# STM32WB55_Sensor_MCU.net
KiCad netlist of a schematic drawn in Altium Designer
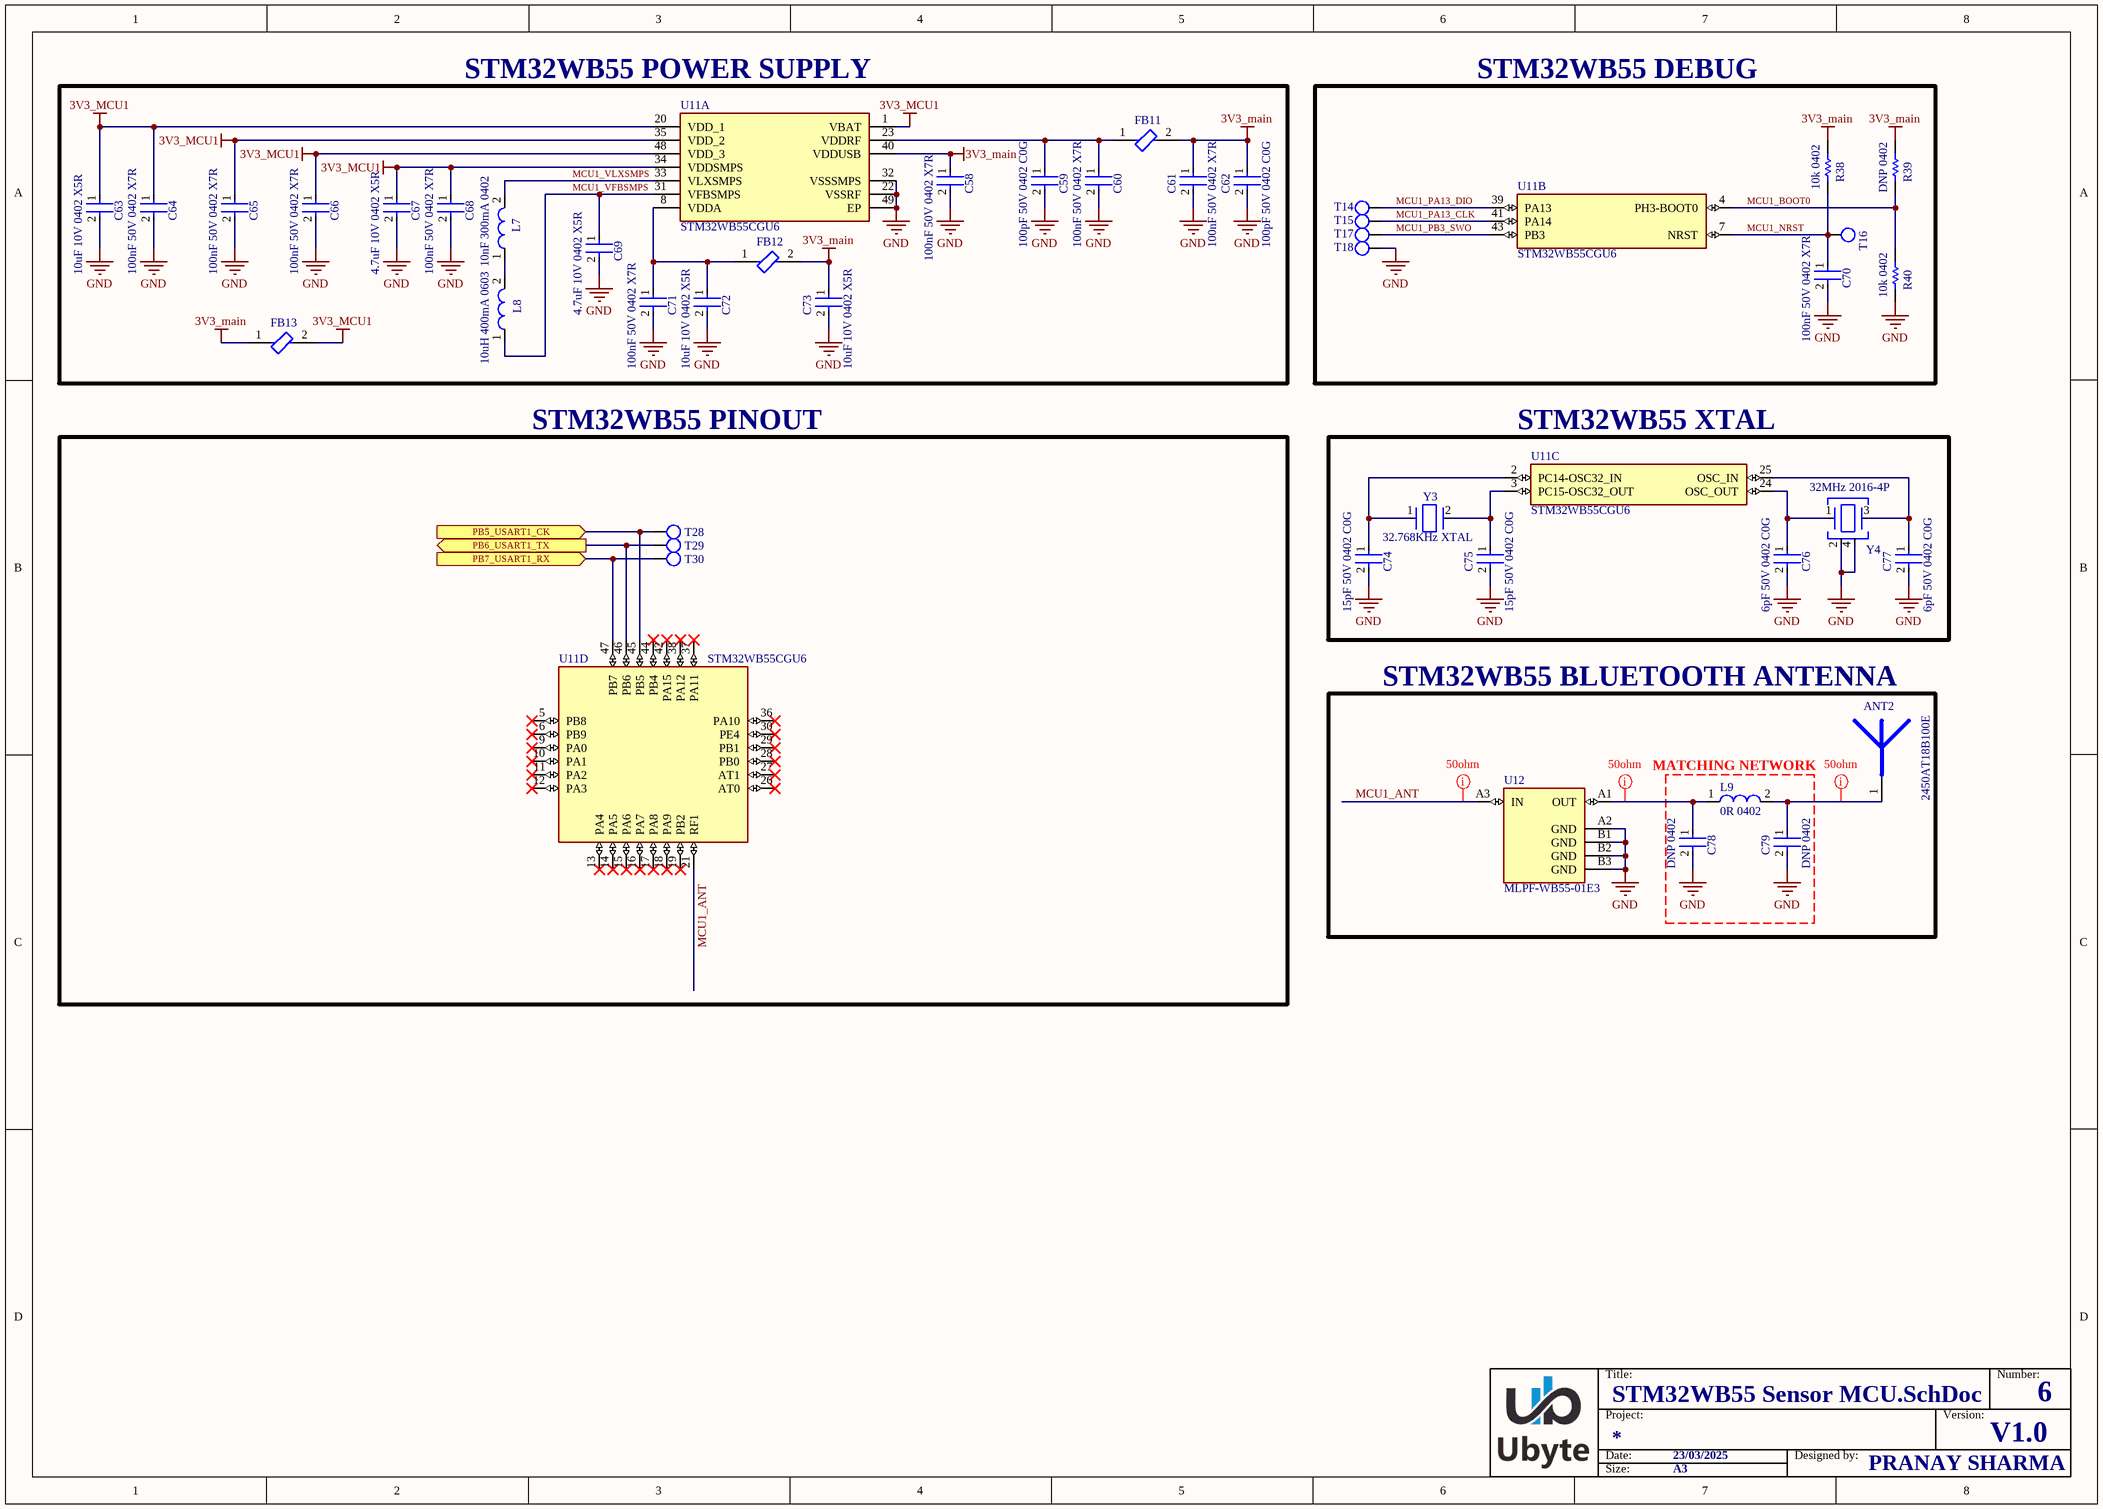
[diagram p0: STM32WB55 Sensor MCU.SchDoc]

(export (version "E")
  (design (tool "Eeschema 10.0.6"))
  (components
    (comp (ref "ANT2")
      (value "2450AT18B100E")
      (footprint "Miscellaneous_Lib:2450AT18B100E IPC-C")
      (libsource (lib "Miscellaneous_Lib") (part "2450AT18B100E"))
    )
    (comp (ref "C58")
      (value "100nF 50V 0402 X7R")
      (footprint "Res, Cap, Ind, LED, FB_Lib:0402 IPC CLASS C CAPACITOR")
      (libsource (lib "Capacitor_Lib") (part "100nF 50V 0402 X7R"))
    )
    (comp (ref "C59")
      (value "100pF 50V 0402 C0G")
      (footprint "Res, Cap, Ind, LED, FB_Lib:0402 IPC CLASS C CAPACITOR")
      (libsource (lib "Capacitor_Lib") (part "100pF 50V 0402 C0G"))
    )
    (comp (ref "C60")
      (value "100nF 50V 0402 X7R")
      (footprint "Res, Cap, Ind, LED, FB_Lib:0402 IPC CLASS C CAPACITOR")
      (libsource (lib "Capacitor_Lib") (part "100nF 50V 0402 X7R"))
    )
    (comp (ref "C61")
      (value "100nF 50V 0402 X7R")
      (footprint "Res, Cap, Ind, LED, FB_Lib:0402 IPC CLASS C CAPACITOR")
      (libsource (lib "Capacitor_Lib") (part "100nF 50V 0402 X7R"))
    )
    (comp (ref "C62")
      (value "100pF 50V 0402 C0G")
      (footprint "Res, Cap, Ind, LED, FB_Lib:0402 IPC CLASS C CAPACITOR")
      (libsource (lib "Capacitor_Lib") (part "100pF 50V 0402 C0G"))
    )
    (comp (ref "C63")
      (value "10uF 10V 0402 X5R")
      (footprint "Res, Cap, Ind, LED, FB_Lib:0402 IPC CLASS C CAPACITOR")
      (libsource (lib "Capacitor_Lib") (part "10uF 10V 0402 X5R"))
    )
    (comp (ref "C64")
      (value "100nF 50V 0402 X7R")
      (footprint "Res, Cap, Ind, LED, FB_Lib:0402 IPC CLASS C CAPACITOR")
      (libsource (lib "Capacitor_Lib") (part "100nF 50V 0402 X7R"))
    )
    (comp (ref "C65")
      (value "100nF 50V 0402 X7R")
      (footprint "Res, Cap, Ind, LED, FB_Lib:0402 IPC CLASS C CAPACITOR")
      (libsource (lib "Capacitor_Lib") (part "100nF 50V 0402 X7R"))
    )
    (comp (ref "C66")
      (value "100nF 50V 0402 X7R")
      (footprint "Res, Cap, Ind, LED, FB_Lib:0402 IPC CLASS C CAPACITOR")
      (libsource (lib "Capacitor_Lib") (part "100nF 50V 0402 X7R"))
    )
    (comp (ref "C67")
      (value "4.7uF 10V 0402 X5R")
      (footprint "Res, Cap, Ind, LED, FB_Lib:0402 IPC CLASS C CAPACITOR")
      (libsource (lib "Capacitor_Lib") (part "4.7uF 10V 0402 X5R"))
    )
    (comp (ref "C68")
      (value "100nF 50V 0402 X7R")
      (footprint "Res, Cap, Ind, LED, FB_Lib:0402 IPC CLASS C CAPACITOR")
      (libsource (lib "Capacitor_Lib") (part "100nF 50V 0402 X7R"))
    )
    (comp (ref "C69")
      (value "4.7uF 10V 0402 X5R")
      (footprint "Res, Cap, Ind, LED, FB_Lib:0402 IPC CLASS C CAPACITOR")
      (libsource (lib "Capacitor_Lib") (part "4.7uF 10V 0402 X5R"))
    )
    (comp (ref "C70")
      (value "100nF 50V 0402 X7R")
      (footprint "Res, Cap, Ind, LED, FB_Lib:0402 IPC CLASS C CAPACITOR")
      (libsource (lib "Capacitor_Lib") (part "100nF 50V 0402 X7R"))
    )
    (comp (ref "C71")
      (value "100nF 50V 0402 X7R")
      (footprint "Res, Cap, Ind, LED, FB_Lib:0402 IPC CLASS C CAPACITOR")
      (libsource (lib "Capacitor_Lib") (part "100nF 50V 0402 X7R"))
    )
    (comp (ref "C72")
      (value "10uF 10V 0402 X5R")
      (footprint "Res, Cap, Ind, LED, FB_Lib:0402 IPC CLASS C CAPACITOR")
      (libsource (lib "Capacitor_Lib") (part "10uF 10V 0402 X5R"))
    )
    (comp (ref "C73")
      (value "10uF 10V 0402 X5R")
      (footprint "Res, Cap, Ind, LED, FB_Lib:0402 IPC CLASS C CAPACITOR")
      (libsource (lib "Capacitor_Lib") (part "10uF 10V 0402 X5R"))
    )
    (comp (ref "C74")
      (value "15pF 50V 0402 C0G")
      (footprint "Res, Cap, Ind, LED, FB_Lib:0402 IPC CLASS C CAPACITOR")
      (libsource (lib "Capacitor_Lib") (part "15pF 50V 0402 C0G"))
    )
    (comp (ref "C75")
      (value "15pF 50V 0402 C0G")
      (footprint "Res, Cap, Ind, LED, FB_Lib:0402 IPC CLASS C CAPACITOR")
      (libsource (lib "Capacitor_Lib") (part "15pF 50V 0402 C0G"))
    )
    (comp (ref "C76")
      (value "6pF 50V 0402 C0G")
      (footprint "Res, Cap, Ind, LED, FB_Lib:0402 IPC CLASS C CAPACITOR")
      (libsource (lib "Capacitor_Lib") (part "6pF 50V 0402 C0G"))
    )
    (comp (ref "C77")
      (value "6pF 50V 0402 C0G")
      (footprint "Res, Cap, Ind, LED, FB_Lib:0402 IPC CLASS C CAPACITOR")
      (libsource (lib "Capacitor_Lib") (part "6pF 50V 0402 C0G"))
    )
    (comp (ref "C78")
      (value "DNP 0402")
      (footprint "Res, Cap, Ind, LED, FB_Lib:0402 IPC CLASS C CAPACITOR")
      (libsource (lib "Capacitor_Lib") (part "100nF 50V 0402 X7R"))
    )
    (comp (ref "C79")
      (value "DNP 0402")
      (footprint "Res, Cap, Ind, LED, FB_Lib:0402 IPC CLASS C CAPACITOR")
      (libsource (lib "Capacitor_Lib") (part "100nF 50V 0402 X7R"))
    )
    (comp (ref "FB11")
      (value "BLM15AX102SN1D")
      (footprint "Res, Cap, Ind, LED, FB_Lib:0402 IPC CLASS C FERRITE BEAD")
      (libsource (lib "Ferrite_Bead_Lib") (part "BLM15AX102SN1D"))
    )
    (comp (ref "FB12")
      (value "BLM15AX102SN1D")
      (footprint "Res, Cap, Ind, LED, FB_Lib:0402 IPC CLASS C FERRITE BEAD")
      (libsource (lib "Ferrite_Bead_Lib") (part "BLM15AX102SN1D"))
    )
    (comp (ref "FB13")
      (value "BLM15AX102SN1D")
      (footprint "Res, Cap, Ind, LED, FB_Lib:0402 IPC CLASS C FERRITE BEAD")
      (libsource (lib "Ferrite_Bead_Lib") (part "BLM15AX102SN1D"))
    )
    (comp (ref "L7")
      (value "10nF 300mA 0402")
      (footprint "Res, Cap, Ind, LED, FB_Lib:0402 IPC CLASS C FERRITE BEAD")
      (libsource (lib "Inductor_Lib") (part "SDCL1005C10NJTDF"))
    )
    (comp (ref "L8")
      (value "10uH 400mA 0603")
      (footprint "Res, Cap, Ind, LED, FB_Lib:0603 IPC CLASS C INDUCTOR")
      (libsource (lib "Inductor_Lib") (part "MGFL1608F100MT-LF"))
    )
    (comp (ref "L9")
      (value "0R 0402")
      (footprint "Res, Cap, Ind, LED, FB_Lib:0402 IPC CLASS C FERRITE BEAD")
      (libsource (lib "Inductor_Lib") (part "SDCL1005C10NJTDF"))
    )
    (comp (ref "R38")
      (value "10k 0402")
      (footprint "Res, Cap, Ind, LED, FB_Lib:0402 IPC CLASS C RESISTOR")
      (libsource (lib "Resistor_Lib") (part "10k 1% 0402"))
    )
    (comp (ref "R39")
      (value "DNP 0402")
      (footprint "Res, Cap, Ind, LED, FB_Lib:0402 IPC CLASS C RESISTOR")
      (libsource (lib "Resistor_Lib") (part "0R 1% 0402"))
    )
    (comp (ref "R40")
      (value "10k 0402")
      (footprint "Res, Cap, Ind, LED, FB_Lib:0402 IPC CLASS C RESISTOR")
      (libsource (lib "Resistor_Lib") (part "10k 1% 0402"))
    )
    (comp (ref "T14")
      (value "Test Point TH")
      (footprint "Miscellaneous_Lib:Test Point TH")
      (libsource (lib "Miscellaneous_Lib") (part "Test Point TH"))
    )
    (comp (ref "T15")
      (value "Test Point TH")
      (footprint "Miscellaneous_Lib:Test Point TH")
      (libsource (lib "Miscellaneous_Lib") (part "Test Point TH"))
    )
    (comp (ref "T16")
      (value "Test Point TH")
      (footprint "Miscellaneous_Lib:Test Point TH")
      (libsource (lib "Miscellaneous_Lib") (part "Test Point TH"))
    )
    (comp (ref "T17")
      (value "Test Point TH")
      (footprint "Miscellaneous_Lib:Test Point TH")
      (libsource (lib "Miscellaneous_Lib") (part "Test Point TH"))
    )
    (comp (ref "T18")
      (value "Test Point TH")
      (footprint "Miscellaneous_Lib:Test Point TH")
      (libsource (lib "Miscellaneous_Lib") (part "Test Point TH"))
    )
    (comp (ref "T28")
      (value "TP")
      (footprint "Miscellaneous_Lib:Testpoint1")
      (libsource (lib "Miscellaneous_Lib") (part "Testpoint1"))
    )
    (comp (ref "T29")
      (value "TP")
      (footprint "Miscellaneous_Lib:Testpoint1")
      (libsource (lib "Miscellaneous_Lib") (part "Testpoint1"))
    )
    (comp (ref "T30")
      (value "TP")
      (footprint "Miscellaneous_Lib:Testpoint1")
      (libsource (lib "Miscellaneous_Lib") (part "Testpoint1"))
    )
    (comp (ref "U11")
      (value "STM32WB55CGU6")
      (footprint "MCU_MPU_Lib:UFQFPN48 IPC-C")
      (libsource (lib "MCU_MPU_Lib") (part "STM32WB55CGU6"))
    )
    (comp (ref "U12")
      (value "MLPF-WB55-01E3")
      (footprint "Miscellaneous_Lib:MLPF-WB55-01E3")
      (libsource (lib "Miscellaneous_Lib") (part "MLPF-WB55-01E3"))
    )
    (comp (ref "Y3")
      (value "32.768KHz XTAL")
      (footprint "Crystals_and_Oscillators_Lib:SMD3215-2P IPC-C")
      (libsource (lib "Crystals_and_Oscillators_Lib") (part "H31003271C2070CY"))
    )
    (comp (ref "Y4")
      (value "32MHz 2016-4P")
      (footprint "Crystals_and_Oscillators_Lib:SMD2016-4P IPC-C")
      (libsource (lib "Crystals_and_Oscillators_Lib") (part "32MHz 2016-4P"))
    )
  )
  (nets
    (net (code "1") (name "/MCU1_ANT") (class "Default")
      (node (ref "U11") (pin "21") (pinfunction "RF1_21") (pintype "bidirectional"))
      (node (ref "U12") (pin "A3") (pinfunction "IN_A3") (pintype "bidirectional"))
    )
    (net (code "2") (name "/MCU1_BOOT0") (class "Default")
      (node (ref "R39") (pin "1") (pinfunction "1_1") (pintype "passive"))
      (node (ref "R40") (pin "2") (pinfunction "2_2") (pintype "passive"))
      (node (ref "U11") (pin "4") (pinfunction "PH3-BOOT0_4") (pintype "bidirectional"))
    )
    (net (code "3") (name "/MCU1_NRST") (class "Default")
      (node (ref "C70") (pin "1") (pinfunction "1_1") (pintype "passive"))
      (node (ref "R38") (pin "1") (pinfunction "1_1") (pintype "passive"))
      (node (ref "T16") (pin "0") (pinfunction "0_0") (pintype "passive"))
      (node (ref "U11") (pin "7") (pinfunction "NRST_7") (pintype "bidirectional"))
    )
    (net (code "4") (name "/MCU1_PA13_CLK") (class "Default")
      (node (ref "T15") (pin "0") (pinfunction "0_0") (pintype "passive"))
      (node (ref "U11") (pin "41") (pinfunction "PA14_41") (pintype "bidirectional"))
    )
    (net (code "5") (name "/MCU1_PA13_DIO") (class "Default")
      (node (ref "T14") (pin "0") (pinfunction "0_0") (pintype "passive"))
      (node (ref "U11") (pin "39") (pinfunction "PA13_39") (pintype "bidirectional"))
    )
    (net (code "6") (name "/MCU1_PB3_SWO") (class "Default")
      (node (ref "T17") (pin "0") (pinfunction "0_0") (pintype "passive"))
      (node (ref "U11") (pin "43") (pinfunction "PB3_43") (pintype "bidirectional"))
    )
    (net (code "7") (name "/MCU1_VFBSMPS") (class "Default")
      (node (ref "C69") (pin "1") (pinfunction "1_1") (pintype "passive"))
      (node (ref "L8") (pin "1") (pinfunction "1_1") (pintype "passive"))
      (node (ref "U11") (pin "31") (pinfunction "VFBSMPS_31") (pintype "power_in"))
    )
    (net (code "8") (name "/MCU1_VLXSMPS") (class "Default")
      (node (ref "L7") (pin "2") (pinfunction "2_2") (pintype "passive"))
      (node (ref "U11") (pin "33") (pinfunction "VLXSMPS_33") (pintype "power_in"))
    )
    (net (code "9") (name "/PB5_USART1_CK") (class "Default")
      (node (ref "T28") (pin "0") (pinfunction "0_0") (pintype "passive"))
      (node (ref "U11") (pin "45") (pinfunction "PB5_45") (pintype "bidirectional"))
    )
    (net (code "10") (name "/PB6_USART1_TX") (class "Default")
      (node (ref "T29") (pin "0") (pinfunction "0_0") (pintype "passive"))
      (node (ref "U11") (pin "46") (pinfunction "PB6_46") (pintype "bidirectional"))
    )
    (net (code "11") (name "/PB7_USART1_RX") (class "Default")
      (node (ref "T30") (pin "0") (pinfunction "0_0") (pintype "passive"))
      (node (ref "U11") (pin "47") (pinfunction "PB7_47") (pintype "bidirectional"))
    )
    (net (code "12") (name "3V3_MCU1") (class "Default")
      (node (ref "C63") (pin "1") (pinfunction "1_1") (pintype "passive"))
      (node (ref "C64") (pin "1") (pinfunction "1_1") (pintype "passive"))
      (node (ref "C65") (pin "1") (pinfunction "1_1") (pintype "passive"))
      (node (ref "C66") (pin "1") (pinfunction "1_1") (pintype "passive"))
      (node (ref "C67") (pin "1") (pinfunction "1_1") (pintype "passive"))
      (node (ref "C68") (pin "1") (pinfunction "1_1") (pintype "passive"))
      (node (ref "FB13") (pin "2") (pinfunction "2_2") (pintype "passive"))
      (node (ref "U11") (pin "1") (pinfunction "VBAT_1") (pintype "power_in"))
      (node (ref "U11") (pin "20") (pinfunction "VDD_1_20") (pintype "power_in"))
      (node (ref "U11") (pin "34") (pinfunction "VDDSMPS_34") (pintype "power_in"))
      (node (ref "U11") (pin "35") (pinfunction "VDD_2_35") (pintype "power_in"))
      (node (ref "U11") (pin "48") (pinfunction "VDD_3_48") (pintype "power_in"))
    )
    (net (code "13") (name "3V3_main") (class "Default")
      (node (ref "C58") (pin "1") (pinfunction "1_1") (pintype "passive"))
      (node (ref "C61") (pin "1") (pinfunction "1_1") (pintype "passive"))
      (node (ref "C62") (pin "1") (pinfunction "1_1") (pintype "passive"))
      (node (ref "C73") (pin "1") (pinfunction "1_1") (pintype "passive"))
      (node (ref "FB11") (pin "2") (pinfunction "2_2") (pintype "passive"))
      (node (ref "FB12") (pin "2") (pinfunction "2_2") (pintype "passive"))
      (node (ref "FB13") (pin "1") (pinfunction "1_1") (pintype "passive"))
      (node (ref "R38") (pin "2") (pinfunction "2_2") (pintype "passive"))
      (node (ref "R39") (pin "2") (pinfunction "2_2") (pintype "passive"))
      (node (ref "U11") (pin "40") (pinfunction "VDDUSB_40") (pintype "power_in"))
    )
    (net (code "14") (name "GND") (class "Default")
      (node (ref "C58") (pin "2") (pinfunction "2_2") (pintype "passive"))
      (node (ref "C59") (pin "2") (pinfunction "2_2") (pintype "passive"))
      (node (ref "C60") (pin "2") (pinfunction "2_2") (pintype "passive"))
      (node (ref "C61") (pin "2") (pinfunction "2_2") (pintype "passive"))
      (node (ref "C62") (pin "2") (pinfunction "2_2") (pintype "passive"))
      (node (ref "C63") (pin "2") (pinfunction "2_2") (pintype "passive"))
      (node (ref "C64") (pin "2") (pinfunction "2_2") (pintype "passive"))
      (node (ref "C65") (pin "2") (pinfunction "2_2") (pintype "passive"))
      (node (ref "C66") (pin "2") (pinfunction "2_2") (pintype "passive"))
      (node (ref "C67") (pin "2") (pinfunction "2_2") (pintype "passive"))
      (node (ref "C68") (pin "2") (pinfunction "2_2") (pintype "passive"))
      (node (ref "C69") (pin "2") (pinfunction "2_2") (pintype "passive"))
      (node (ref "C70") (pin "2") (pinfunction "2_2") (pintype "passive"))
      (node (ref "C71") (pin "2") (pinfunction "2_2") (pintype "passive"))
      (node (ref "C72") (pin "2") (pinfunction "2_2") (pintype "passive"))
      (node (ref "C73") (pin "2") (pinfunction "2_2") (pintype "passive"))
      (node (ref "C74") (pin "2") (pinfunction "2_2") (pintype "passive"))
      (node (ref "C75") (pin "2") (pinfunction "2_2") (pintype "passive"))
      (node (ref "C76") (pin "2") (pinfunction "2_2") (pintype "passive"))
      (node (ref "C77") (pin "2") (pinfunction "2_2") (pintype "passive"))
      (node (ref "C78") (pin "2") (pinfunction "2_2") (pintype "passive"))
      (node (ref "C79") (pin "2") (pinfunction "2_2") (pintype "passive"))
      (node (ref "R40") (pin "1") (pinfunction "1_1") (pintype "passive"))
      (node (ref "T18") (pin "0") (pinfunction "0_0") (pintype "passive"))
      (node (ref "U11") (pin "22") (pinfunction "VSSRF_22") (pintype "power_in"))
      (node (ref "U11") (pin "32") (pinfunction "VSSSMPS_32") (pintype "power_in"))
      (node (ref "U11") (pin "49") (pinfunction "EP_49") (pintype "power_in"))
      (node (ref "U12") (pin "A2") (pinfunction "GND_A2") (pintype "power_in"))
      (node (ref "U12") (pin "B1") (pinfunction "GND_B1") (pintype "power_in"))
      (node (ref "U12") (pin "B2") (pinfunction "GND_B2") (pintype "power_in"))
      (node (ref "U12") (pin "B3") (pinfunction "GND_B3") (pintype "power_in"))
      (node (ref "Y4") (pin "2") (pinfunction "2_2") (pintype "passive"))
      (node (ref "Y4") (pin "4") (pinfunction "4_4") (pintype "passive"))
    )
    (net (code "15") (name "Net-(ANT2-Pad1)") (class "Default")
      (node (ref "ANT2") (pin "1") (pinfunction "1_1") (pintype "passive"))
      (node (ref "C79") (pin "1") (pinfunction "1_1") (pintype "passive"))
      (node (ref "L9") (pin "2") (pinfunction "2_2") (pintype "passive"))
    )
    (net (code "16") (name "Net-(L7-Pad1)") (class "Default")
      (node (ref "L7") (pin "1") (pinfunction "1_1") (pintype "passive"))
      (node (ref "L8") (pin "2") (pinfunction "2_2") (pintype "passive"))
    )
    (net (code "17") (name "Net-(U11A-VDDA)") (class "Default")
      (node (ref "C71") (pin "1") (pinfunction "1_1") (pintype "passive"))
      (node (ref "C72") (pin "1") (pinfunction "1_1") (pintype "passive"))
      (node (ref "FB12") (pin "1") (pinfunction "1_1") (pintype "passive"))
      (node (ref "U11") (pin "8") (pinfunction "VDDA_8") (pintype "power_in"))
    )
    (net (code "18") (name "Net-(U11A-VDDRF)") (class "Default")
      (node (ref "C59") (pin "1") (pinfunction "1_1") (pintype "passive"))
      (node (ref "C60") (pin "1") (pinfunction "1_1") (pintype "passive"))
      (node (ref "FB11") (pin "1") (pinfunction "1_1") (pintype "passive"))
      (node (ref "U11") (pin "23") (pinfunction "VDDRF_23") (pintype "power_in"))
    )
    (net (code "19") (name "Net-(U11C-OSC_IN)") (class "Default")
      (node (ref "C77") (pin "1") (pinfunction "1_1") (pintype "passive"))
      (node (ref "U11") (pin "25") (pinfunction "OSC_IN_25") (pintype "bidirectional"))
      (node (ref "Y4") (pin "3") (pinfunction "2_3") (pintype "passive"))
    )
    (net (code "20") (name "Net-(U11C-OSC_OUT)") (class "Default")
      (node (ref "C76") (pin "1") (pinfunction "1_1") (pintype "passive"))
      (node (ref "U11") (pin "24") (pinfunction "OSC_OUT_24") (pintype "bidirectional"))
      (node (ref "Y4") (pin "1") (pinfunction "1_1") (pintype "passive"))
    )
    (net (code "21") (name "Net-(U11C-PC14-OSC32_IN)") (class "Default")
      (node (ref "C74") (pin "1") (pinfunction "1_1") (pintype "passive"))
      (node (ref "U11") (pin "2") (pinfunction "PC14-OSC32_IN_2") (pintype "bidirectional"))
      (node (ref "Y3") (pin "1") (pinfunction "1_1") (pintype "passive"))
    )
    (net (code "22") (name "Net-(U11C-PC15-OSC32_OUT)") (class "Default")
      (node (ref "C75") (pin "1") (pinfunction "1_1") (pintype "passive"))
      (node (ref "U11") (pin "3") (pinfunction "PC15-OSC32_OUT_3") (pintype "bidirectional"))
      (node (ref "Y3") (pin "2") (pinfunction "2_2") (pintype "passive"))
    )
    (net (code "23") (name "Net-(U12-OUT)") (class "Default")
      (node (ref "C78") (pin "1") (pinfunction "1_1") (pintype "passive"))
      (node (ref "L9") (pin "1") (pinfunction "1_1") (pintype "passive"))
      (node (ref "U12") (pin "A1") (pinfunction "OUT_A1") (pintype "bidirectional"))
    )
    (net (code "24") (name "unconnected-(U11D-AT0-Pad26)") (class "Default")
      (node (ref "U11") (pin "26") (pinfunction "AT0_26") (pintype "bidirectional+no_connect"))
    )
    (net (code "25") (name "unconnected-(U11D-AT1-Pad27)") (class "Default")
      (node (ref "U11") (pin "27") (pinfunction "AT1_27") (pintype "bidirectional+no_connect"))
    )
    (net (code "26") (name "unconnected-(U11D-PA0-Pad9)") (class "Default")
      (node (ref "U11") (pin "9") (pinfunction "PA0_9") (pintype "bidirectional+no_connect"))
    )
    (net (code "27") (name "unconnected-(U11D-PA1-Pad10)") (class "Default")
      (node (ref "U11") (pin "10") (pinfunction "PA1_10") (pintype "bidirectional+no_connect"))
    )
    (net (code "28") (name "unconnected-(U11D-PA2-Pad11)") (class "Default")
      (node (ref "U11") (pin "11") (pinfunction "PA2_11") (pintype "bidirectional+no_connect"))
    )
    (net (code "29") (name "unconnected-(U11D-PA3-Pad12)") (class "Default")
      (node (ref "U11") (pin "12") (pinfunction "PA3_12") (pintype "bidirectional+no_connect"))
    )
    (net (code "30") (name "unconnected-(U11D-PA4-Pad13)") (class "Default")
      (node (ref "U11") (pin "13") (pinfunction "PA4_13") (pintype "bidirectional+no_connect"))
    )
    (net (code "31") (name "unconnected-(U11D-PA5-Pad14)") (class "Default")
      (node (ref "U11") (pin "14") (pinfunction "PA5_14") (pintype "bidirectional+no_connect"))
    )
    (net (code "32") (name "unconnected-(U11D-PA6-Pad15)") (class "Default")
      (node (ref "U11") (pin "15") (pinfunction "PA6_15") (pintype "bidirectional+no_connect"))
    )
    (net (code "33") (name "unconnected-(U11D-PA7-Pad16)") (class "Default")
      (node (ref "U11") (pin "16") (pinfunction "PA7_16") (pintype "bidirectional+no_connect"))
    )
    (net (code "34") (name "unconnected-(U11D-PA8-Pad17)") (class "Default")
      (node (ref "U11") (pin "17") (pinfunction "PA8_17") (pintype "bidirectional+no_connect"))
    )
    (net (code "35") (name "unconnected-(U11D-PA9-Pad18)") (class "Default")
      (node (ref "U11") (pin "18") (pinfunction "PA9_18") (pintype "bidirectional+no_connect"))
    )
    (net (code "36") (name "unconnected-(U11D-PA10-Pad36)") (class "Default")
      (node (ref "U11") (pin "36") (pinfunction "PA10_36") (pintype "bidirectional+no_connect"))
    )
    (net (code "37") (name "unconnected-(U11D-PA11-Pad37)") (class "Default")
      (node (ref "U11") (pin "37") (pinfunction "PA11_37") (pintype "bidirectional+no_connect"))
    )
    (net (code "38") (name "unconnected-(U11D-PA12-Pad38)") (class "Default")
      (node (ref "U11") (pin "38") (pinfunction "PA12_38") (pintype "bidirectional+no_connect"))
    )
    (net (code "39") (name "unconnected-(U11D-PA15-Pad42)") (class "Default")
      (node (ref "U11") (pin "42") (pinfunction "PA15_42") (pintype "bidirectional+no_connect"))
    )
    (net (code "40") (name "unconnected-(U11D-PB0-Pad28)") (class "Default")
      (node (ref "U11") (pin "28") (pinfunction "PB0_28") (pintype "bidirectional+no_connect"))
    )
    (net (code "41") (name "unconnected-(U11D-PB1-Pad29)") (class "Default")
      (node (ref "U11") (pin "29") (pinfunction "PB1_29") (pintype "bidirectional+no_connect"))
    )
    (net (code "42") (name "unconnected-(U11D-PB2-Pad19)") (class "Default")
      (node (ref "U11") (pin "19") (pinfunction "PB2_19") (pintype "bidirectional+no_connect"))
    )
    (net (code "43") (name "unconnected-(U11D-PB4-Pad44)") (class "Default")
      (node (ref "U11") (pin "44") (pinfunction "PB4_44") (pintype "bidirectional+no_connect"))
    )
    (net (code "44") (name "unconnected-(U11D-PB8-Pad5)") (class "Default")
      (node (ref "U11") (pin "5") (pinfunction "PB8_5") (pintype "bidirectional+no_connect"))
    )
    (net (code "45") (name "unconnected-(U11D-PB9-Pad6)") (class "Default")
      (node (ref "U11") (pin "6") (pinfunction "PB9_6") (pintype "bidirectional+no_connect"))
    )
    (net (code "46") (name "unconnected-(U11D-PE4-Pad30)") (class "Default")
      (node (ref "U11") (pin "30") (pinfunction "PE4_30") (pintype "bidirectional+no_connect"))
    )
  )
)
